# EL_Sequencer.net
KiCad netlist of a schematic drawn in EAGLE
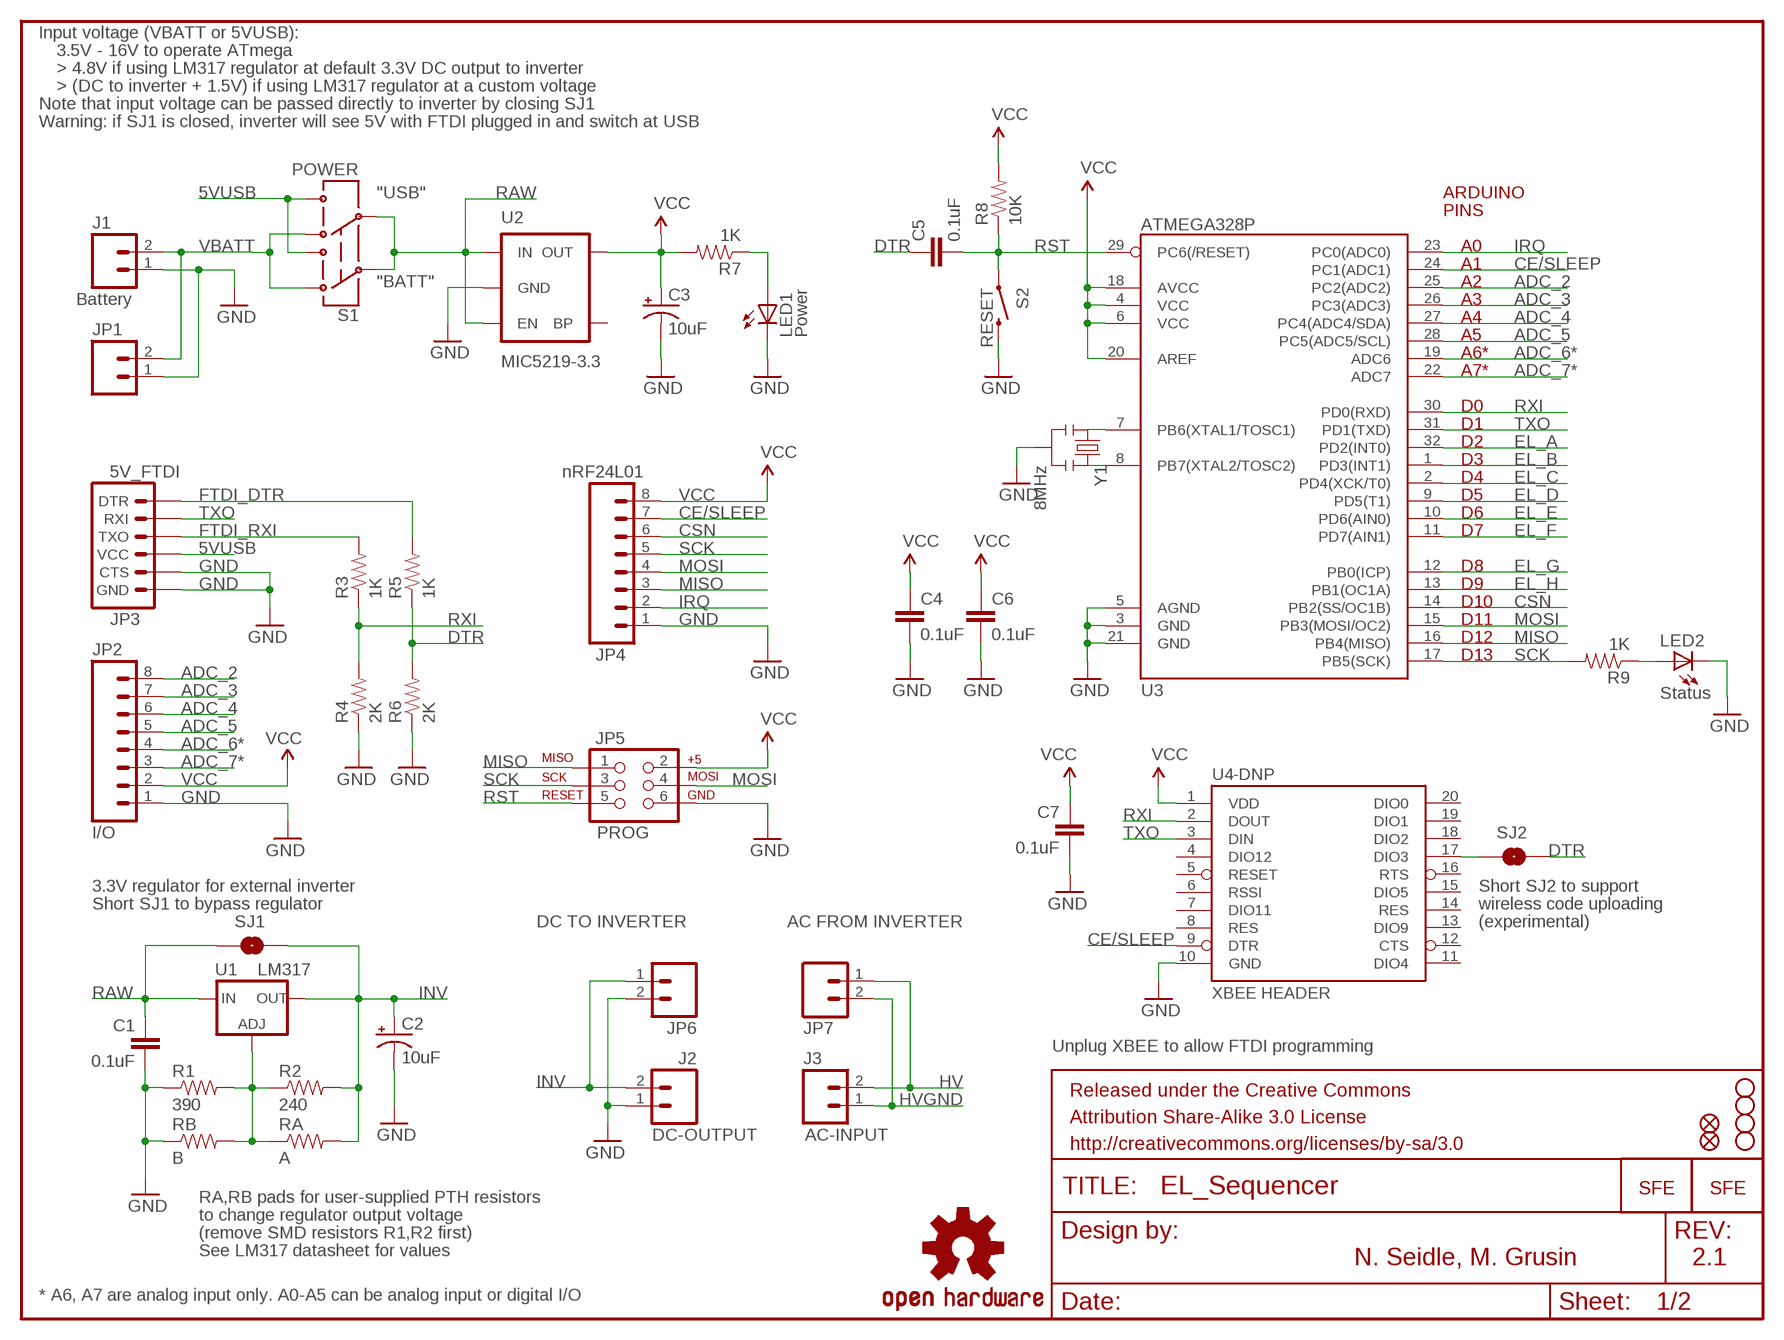
[diagram p0: schematic, sheet 1]
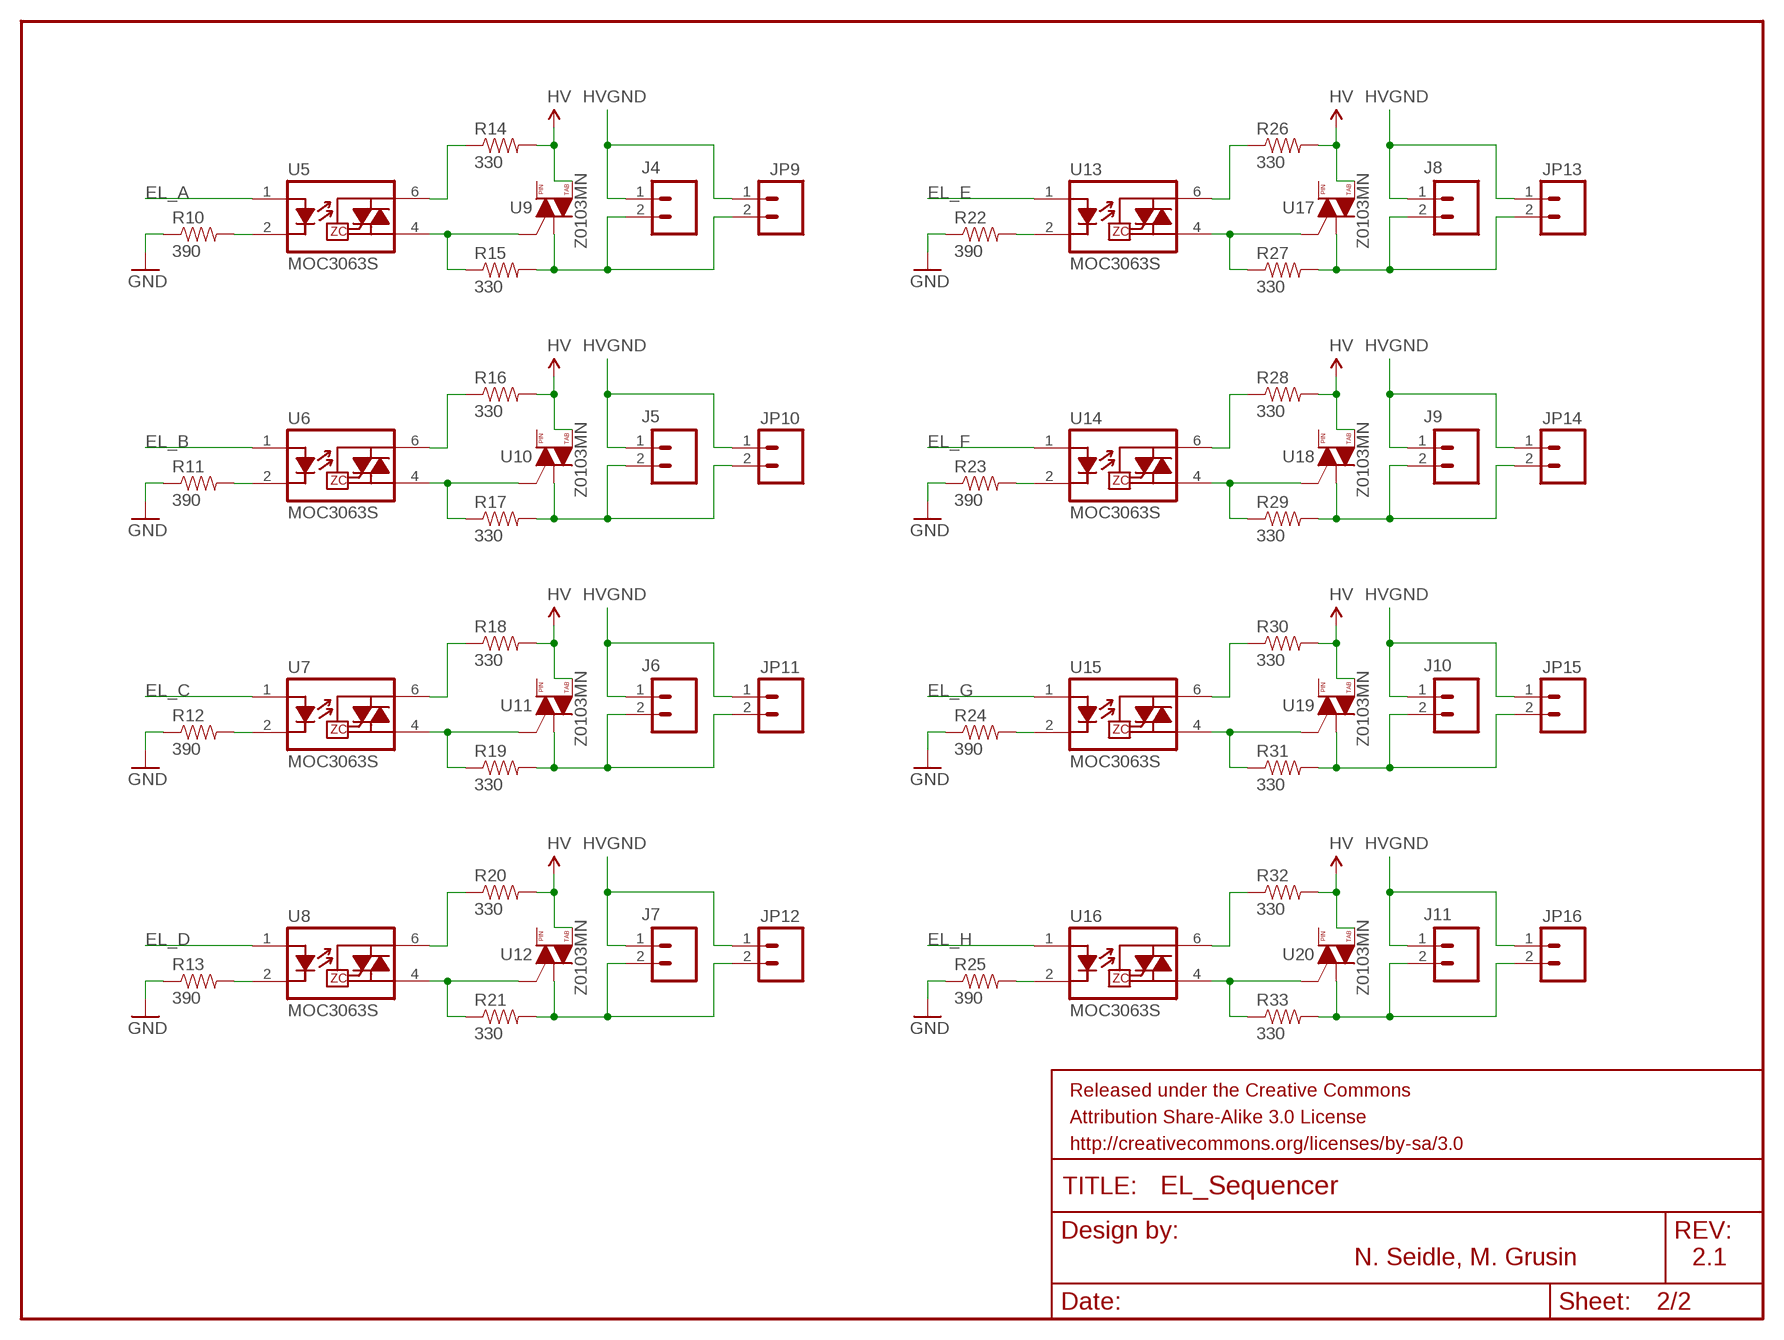
[diagram p1: schematic, sheet 2]

(export (version "E")
  (design (tool "Eeschema 10.0.6"))
  (components
    (comp (ref "C1")
      (value "0.1uF")
      (footprint "eagle-import:0402-CAP")
      (libsource (lib "eagle-import") (part "CAP0402-CAP"))
    )
    (comp (ref "C2")
      (value "10uF")
      (footprint "eagle-import:EIA3216")
      (libsource (lib "eagle-import") (part "CAP_POL1206"))
    )
    (comp (ref "C3")
      (value "10uF")
      (footprint "eagle-import:EIA3216")
      (libsource (lib "eagle-import") (part "CAP_POL1206"))
    )
    (comp (ref "C4")
      (value "0.1uF")
      (footprint "eagle-import:0402-CAP")
      (libsource (lib "eagle-import") (part "CAP0402-CAP"))
    )
    (comp (ref "C5")
      (value "0.1uF")
      (footprint "eagle-import:0402-CAP")
      (libsource (lib "eagle-import") (part "CAP0402-CAP"))
    )
    (comp (ref "C6")
      (value "0.1uF")
      (footprint "eagle-import:0402-CAP")
      (libsource (lib "eagle-import") (part "CAP0402-CAP"))
    )
    (comp (ref "C7")
      (value "0.1uF")
      (footprint "eagle-import:0402-CAP")
      (libsource (lib "eagle-import") (part "CAP0402-CAP"))
    )
    (comp (ref "FRAME1")
      (value "FRAME-LETTER")
      (footprint "eagle-import:CREATIVE_COMMONS")
      (libsource (lib "eagle-import") (part "FRAME-LETTER"))
    )
    (comp (ref "J1")
      (value "Battery")
      (footprint "eagle-import:JST-2-SMD")
      (libsource (lib "eagle-import") (part "M02-JST-2MM-SMT"))
    )
    (comp (ref "J2")
      (value "DC-OUTPUT")
      (footprint "eagle-import:JST-2-SMD")
      (libsource (lib "eagle-import") (part "M02-JST-2MM-SMT"))
    )
    (comp (ref "J3")
      (value "AC-INPUT")
      (footprint "eagle-import:JST-2-SMD")
      (libsource (lib "eagle-import") (part "M02-JST-2MM-SMT"))
    )
    (comp (ref "JP1")
      (value "M02PTH")
      (footprint "eagle-import:1X02")
      (libsource (lib "eagle-import") (part "M02PTH"))
    )
    (comp (ref "JP2")
      (value "I/O")
      (footprint "eagle-import:1X08_ROUND")
      (libsource (lib "eagle-import") (part "M08_ROUND"))
    )
    (comp (ref "JP3")
      (value "5V_FTDI")
      (footprint "eagle-import:1X06")
      (libsource (lib "eagle-import") (part "ARDUINO_SERIAL_PROGRAMPTH"))
    )
    (comp (ref "JP4")
      (value "nRF24L01")
      (footprint "eagle-import:1X08")
      (libsource (lib "eagle-import") (part "M081X08"))
    )
    (comp (ref "JP5")
      (value "PROG")
      (footprint "eagle-import:2X3")
      (libsource (lib "eagle-import") (part "AVR_SPI_PRG_6PTH"))
    )
    (comp (ref "JP6")
      (value "M02PTH")
      (footprint "eagle-import:1X02")
      (libsource (lib "eagle-import") (part "M02PTH"))
    )
    (comp (ref "JP7")
      (value "M02PTH")
      (footprint "eagle-import:1X02")
      (libsource (lib "eagle-import") (part "M02PTH"))
    )
    (comp (ref "JP8")
      (value "LOGO-SFESK")
      (footprint "eagle-import:SFE-LOGO-FLAME")
      (libsource (lib "eagle-import") (part "SparkFun-Aesthetics_LOGO-SFESK"))
    )
    (comp (ref "LED1")
      (value "Power")
      (footprint "eagle-import:LED-0603")
      (libsource (lib "eagle-import") (part "LED0603"))
    )
    (comp (ref "LED2")
      (value "Status")
      (footprint "eagle-import:LED-0603")
      (libsource (lib "eagle-import") (part "LED0603"))
    )
    (comp (ref "R1")
      (value "390")
      (footprint "eagle-import:0603-RES")
      (libsource (lib "eagle-import") (part "RESISTOR0603-RES"))
    )
    (comp (ref "R2")
      (value "240")
      (footprint "eagle-import:0603-RES")
      (libsource (lib "eagle-import") (part "RESISTOR0603-RES"))
    )
    (comp (ref "R3")
      (value "1K")
      (footprint "eagle-import:0402-RES")
      (libsource (lib "eagle-import") (part "RESISTOR0402-RES"))
    )
    (comp (ref "R4")
      (value "2K")
      (footprint "eagle-import:0402-RES")
      (libsource (lib "eagle-import") (part "RESISTOR0402-RES"))
    )
    (comp (ref "R5")
      (value "1K")
      (footprint "eagle-import:0402-RES")
      (libsource (lib "eagle-import") (part "RESISTOR0402-RES"))
    )
    (comp (ref "R6")
      (value "2K")
      (footprint "eagle-import:0402-RES")
      (libsource (lib "eagle-import") (part "RESISTOR0402-RES"))
    )
    (comp (ref "R7")
      (value "1K")
      (footprint "eagle-import:0402-RES")
      (libsource (lib "eagle-import") (part "RESISTOR0402-RES"))
    )
    (comp (ref "R8")
      (value "10K")
      (footprint "eagle-import:0402-RES")
      (libsource (lib "eagle-import") (part "RESISTOR0402-RES"))
    )
    (comp (ref "R9")
      (value "1K")
      (footprint "eagle-import:0402-RES")
      (libsource (lib "eagle-import") (part "RESISTOR0402-RES"))
    )
    (comp (ref "RA")
      (value "A")
      (footprint "eagle-import:AXIAL-0.4")
      (libsource (lib "eagle-import") (part "RESISTORPTH-1/4W"))
    )
    (comp (ref "RB")
      (value "B")
      (footprint "eagle-import:AXIAL-0.4")
      (libsource (lib "eagle-import") (part "RESISTORPTH-1/4W"))
    )
    (comp (ref "S1")
      (value "POWER")
      (footprint "eagle-import:AYZ0202")
      (libsource (lib "eagle-import") (part "SWITCH-DPDTSMD"))
    )
    (comp (ref "S2")
      (value "RESET")
      (footprint "eagle-import:TACTILE_SWITCH_SMD")
      (libsource (lib "eagle-import") (part "SWITCH-MOMENTARY-2SMD"))
    )
    (comp (ref "SJ1")
      (value "SOLDERJUMPERROUND")
      (footprint "eagle-import:SJ_ROUND")
      (libsource (lib "eagle-import") (part "SOLDERJUMPERROUND"))
    )
    (comp (ref "SJ2")
      (value "SOLDERJUMPERNO")
      (footprint "eagle-import:SJ_2S-NO")
      (libsource (lib "eagle-import") (part "SOLDERJUMPERNO"))
    )
    (comp (ref "U$1")
      (value "OSHW-LOGOS")
      (footprint "eagle-import:OSHW-LOGO-S")
      (libsource (lib "eagle-import") (part "OSHW-LOGOS"))
    )
    (comp (ref "U$2")
      (value "LOGO-SFENEW")
      (footprint "eagle-import:SFE-NEW-WEBLOGO")
      (libsource (lib "eagle-import") (part "LOGO-SFENEW"))
    )
    (comp (ref "U$3")
      (value "FIDUCIALUFIDUCIAL")
      (footprint "eagle-import:MICRO-FIDUCIAL")
      (libsource (lib "eagle-import") (part "FIDUCIALUFIDUCIAL"))
    )
    (comp (ref "U$4")
      (value "FIDUCIALUFIDUCIAL")
      (footprint "eagle-import:MICRO-FIDUCIAL")
      (libsource (lib "eagle-import") (part "FIDUCIALUFIDUCIAL"))
    )
    (comp (ref "U$5")
      (value "STAND-OFF")
      (footprint "eagle-import:STAND-OFF")
      (libsource (lib "eagle-import") (part "STAND-OFF"))
    )
    (comp (ref "U$6")
      (value "STAND-OFF")
      (footprint "eagle-import:STAND-OFF")
      (libsource (lib "eagle-import") (part "STAND-OFF"))
    )
    (comp (ref "U$7")
      (value "STAND-OFF")
      (footprint "eagle-import:STAND-OFF")
      (libsource (lib "eagle-import") (part "STAND-OFF"))
    )
    (comp (ref "U$8")
      (value "STAND-OFF")
      (footprint "eagle-import:STAND-OFF")
      (libsource (lib "eagle-import") (part "STAND-OFF"))
    )
    (comp (ref "U1")
      (value "LM317")
      (footprint "eagle-import:V-REG_DPACK")
      (libsource (lib "eagle-import") (part "V_REG_317DPACK"))
    )
    (comp (ref "U2")
      (value "MIC5219-3.3")
      (footprint "eagle-import:SOT23-5")
      (libsource (lib "eagle-import") (part "V_REG_LDOSMD"))
    )
    (comp (ref "U3")
      (value "ATMEGA328P")
      (footprint "eagle-import:TQFP32-08")
      (libsource (lib "eagle-import") (part "ATMEGA168"))
    )
    (comp (ref "U4-DNP")
      (value "XBEE HEADER")
      (footprint "eagle-import:XBEE-LONGPAD")
      (libsource (lib "eagle-import") (part "XBEE-1LONGPAD"))
    )
    (comp (ref "Y1")
      (value "8MHz")
      (footprint "eagle-import:RESONATOR-SMD")
      (libsource (lib "eagle-import") (part "RESONATORSMD"))
    )
    (comp (ref "FRAME2")
      (value "FRAME-LETTER")
      (footprint "eagle-import:CREATIVE_COMMONS")
      (libsource (lib "eagle-import") (part "FRAME-LETTER"))
    )
    (comp (ref "J4")
      (value "M02-JST-2MM-SMT")
      (footprint "eagle-import:JST-2-SMD")
      (libsource (lib "eagle-import") (part "M02-JST-2MM-SMT"))
    )
    (comp (ref "J5")
      (value "M02-JST-2MM-SMT")
      (footprint "eagle-import:JST-2-SMD")
      (libsource (lib "eagle-import") (part "M02-JST-2MM-SMT"))
    )
    (comp (ref "J6")
      (value "M02-JST-2MM-SMT")
      (footprint "eagle-import:JST-2-SMD")
      (libsource (lib "eagle-import") (part "M02-JST-2MM-SMT"))
    )
    (comp (ref "J7")
      (value "M02-JST-2MM-SMT")
      (footprint "eagle-import:JST-2-SMD")
      (libsource (lib "eagle-import") (part "M02-JST-2MM-SMT"))
    )
    (comp (ref "J8")
      (value "M02-JST-2MM-SMT")
      (footprint "eagle-import:JST-2-SMD")
      (libsource (lib "eagle-import") (part "M02-JST-2MM-SMT"))
    )
    (comp (ref "J9")
      (value "M02-JST-2MM-SMT")
      (footprint "eagle-import:JST-2-SMD")
      (libsource (lib "eagle-import") (part "M02-JST-2MM-SMT"))
    )
    (comp (ref "J10")
      (value "M02-JST-2MM-SMT")
      (footprint "eagle-import:JST-2-SMD")
      (libsource (lib "eagle-import") (part "M02-JST-2MM-SMT"))
    )
    (comp (ref "J11")
      (value "M02-JST-2MM-SMT")
      (footprint "eagle-import:JST-2-SMD")
      (libsource (lib "eagle-import") (part "M02-JST-2MM-SMT"))
    )
    (comp (ref "JP9")
      (value "M02PTH")
      (footprint "eagle-import:1X02")
      (libsource (lib "eagle-import") (part "M02PTH"))
    )
    (comp (ref "JP10")
      (value "M02PTH")
      (footprint "eagle-import:1X02")
      (libsource (lib "eagle-import") (part "M02PTH"))
    )
    (comp (ref "JP11")
      (value "M02PTH")
      (footprint "eagle-import:1X02")
      (libsource (lib "eagle-import") (part "M02PTH"))
    )
    (comp (ref "JP12")
      (value "M02PTH")
      (footprint "eagle-import:1X02")
      (libsource (lib "eagle-import") (part "M02PTH"))
    )
    (comp (ref "JP13")
      (value "M02PTH")
      (footprint "eagle-import:1X02")
      (libsource (lib "eagle-import") (part "M02PTH"))
    )
    (comp (ref "JP14")
      (value "M02PTH")
      (footprint "eagle-import:1X02")
      (libsource (lib "eagle-import") (part "M02PTH"))
    )
    (comp (ref "JP15")
      (value "M02PTH")
      (footprint "eagle-import:1X02")
      (libsource (lib "eagle-import") (part "M02PTH"))
    )
    (comp (ref "JP16")
      (value "M02PTH")
      (footprint "eagle-import:1X02")
      (libsource (lib "eagle-import") (part "M02PTH"))
    )
    (comp (ref "R10")
      (value "390")
      (footprint "eagle-import:0402-RES")
      (libsource (lib "eagle-import") (part "RESISTOR0402-RES"))
    )
    (comp (ref "R11")
      (value "390")
      (footprint "eagle-import:0402-RES")
      (libsource (lib "eagle-import") (part "RESISTOR0402-RES"))
    )
    (comp (ref "R12")
      (value "390")
      (footprint "eagle-import:0402-RES")
      (libsource (lib "eagle-import") (part "RESISTOR0402-RES"))
    )
    (comp (ref "R13")
      (value "390")
      (footprint "eagle-import:0402-RES")
      (libsource (lib "eagle-import") (part "RESISTOR0402-RES"))
    )
    (comp (ref "R14")
      (value "330")
      (footprint "eagle-import:0603-RES")
      (libsource (lib "eagle-import") (part "RESISTOR0603-RES"))
    )
    (comp (ref "R15")
      (value "330")
      (footprint "eagle-import:0603-RES")
      (libsource (lib "eagle-import") (part "RESISTOR0603-RES"))
    )
    (comp (ref "R16")
      (value "330")
      (footprint "eagle-import:0603-RES")
      (libsource (lib "eagle-import") (part "RESISTOR0603-RES"))
    )
    (comp (ref "R17")
      (value "330")
      (footprint "eagle-import:0603-RES")
      (libsource (lib "eagle-import") (part "RESISTOR0603-RES"))
    )
    (comp (ref "R18")
      (value "330")
      (footprint "eagle-import:0603-RES")
      (libsource (lib "eagle-import") (part "RESISTOR0603-RES"))
    )
    (comp (ref "R19")
      (value "330")
      (footprint "eagle-import:0603-RES")
      (libsource (lib "eagle-import") (part "RESISTOR0603-RES"))
    )
    (comp (ref "R20")
      (value "330")
      (footprint "eagle-import:0603-RES")
      (libsource (lib "eagle-import") (part "RESISTOR0603-RES"))
    )
    (comp (ref "R21")
      (value "330")
      (footprint "eagle-import:0603-RES")
      (libsource (lib "eagle-import") (part "RESISTOR0603-RES"))
    )
    (comp (ref "R22")
      (value "390")
      (footprint "eagle-import:0402-RES")
      (libsource (lib "eagle-import") (part "RESISTOR0402-RES"))
    )
    (comp (ref "R23")
      (value "390")
      (footprint "eagle-import:0402-RES")
      (libsource (lib "eagle-import") (part "RESISTOR0402-RES"))
    )
    (comp (ref "R24")
      (value "390")
      (footprint "eagle-import:0402-RES")
      (libsource (lib "eagle-import") (part "RESISTOR0402-RES"))
    )
    (comp (ref "R25")
      (value "390")
      (footprint "eagle-import:0402-RES")
      (libsource (lib "eagle-import") (part "RESISTOR0402-RES"))
    )
    (comp (ref "R26")
      (value "330")
      (footprint "eagle-import:0603-RES")
      (libsource (lib "eagle-import") (part "RESISTOR0603-RES"))
    )
    (comp (ref "R27")
      (value "330")
      (footprint "eagle-import:0603-RES")
      (libsource (lib "eagle-import") (part "RESISTOR0603-RES"))
    )
    (comp (ref "R28")
      (value "330")
      (footprint "eagle-import:0603-RES")
      (libsource (lib "eagle-import") (part "RESISTOR0603-RES"))
    )
    (comp (ref "R29")
      (value "330")
      (footprint "eagle-import:0603-RES")
      (libsource (lib "eagle-import") (part "RESISTOR0603-RES"))
    )
    (comp (ref "R30")
      (value "330")
      (footprint "eagle-import:0603-RES")
      (libsource (lib "eagle-import") (part "RESISTOR0603-RES"))
    )
    (comp (ref "R31")
      (value "330")
      (footprint "eagle-import:0603-RES")
      (libsource (lib "eagle-import") (part "RESISTOR0603-RES"))
    )
    (comp (ref "R32")
      (value "330")
      (footprint "eagle-import:0603-RES")
      (libsource (lib "eagle-import") (part "RESISTOR0603-RES"))
    )
    (comp (ref "R33")
      (value "330")
      (footprint "eagle-import:0603-RES")
      (libsource (lib "eagle-import") (part "RESISTOR0603-RES"))
    )
    (comp (ref "U5")
      (value "MOC3063S")
      (footprint "eagle-import:DIP8SMD")
      (libsource (lib "eagle-import") (part "MOC3063S"))
    )
    (comp (ref "U6")
      (value "MOC3063S")
      (footprint "eagle-import:DIP8SMD")
      (libsource (lib "eagle-import") (part "MOC3063S"))
    )
    (comp (ref "U7")
      (value "MOC3063S")
      (footprint "eagle-import:DIP8SMD")
      (libsource (lib "eagle-import") (part "MOC3063S"))
    )
    (comp (ref "U8")
      (value "MOC3063S")
      (footprint "eagle-import:DIP8SMD")
      (libsource (lib "eagle-import") (part "MOC3063S"))
    )
    (comp (ref "U9")
      (value "Z0103MN")
      (footprint "eagle-import:SOT223")
      (libsource (lib "eagle-import") (part "TRIACSMD"))
    )
    (comp (ref "U10")
      (value "Z0103MN")
      (footprint "eagle-import:SOT223")
      (libsource (lib "eagle-import") (part "TRIACSMD"))
    )
    (comp (ref "U11")
      (value "Z0103MN")
      (footprint "eagle-import:SOT223")
      (libsource (lib "eagle-import") (part "TRIACSMD"))
    )
    (comp (ref "U12")
      (value "Z0103MN")
      (footprint "eagle-import:SOT223")
      (libsource (lib "eagle-import") (part "TRIACSMD"))
    )
    (comp (ref "U13")
      (value "MOC3063S")
      (footprint "eagle-import:DIP8SMD")
      (libsource (lib "eagle-import") (part "MOC3063S"))
    )
    (comp (ref "U14")
      (value "MOC3063S")
      (footprint "eagle-import:DIP8SMD")
      (libsource (lib "eagle-import") (part "MOC3063S"))
    )
    (comp (ref "U15")
      (value "MOC3063S")
      (footprint "eagle-import:DIP8SMD")
      (libsource (lib "eagle-import") (part "MOC3063S"))
    )
    (comp (ref "U16")
      (value "MOC3063S")
      (footprint "eagle-import:DIP8SMD")
      (libsource (lib "eagle-import") (part "MOC3063S"))
    )
    (comp (ref "U17")
      (value "Z0103MN")
      (footprint "eagle-import:SOT223")
      (libsource (lib "eagle-import") (part "TRIACSMD"))
    )
    (comp (ref "U18")
      (value "Z0103MN")
      (footprint "eagle-import:SOT223")
      (libsource (lib "eagle-import") (part "TRIACSMD"))
    )
    (comp (ref "U19")
      (value "Z0103MN")
      (footprint "eagle-import:SOT223")
      (libsource (lib "eagle-import") (part "TRIACSMD"))
    )
    (comp (ref "U20")
      (value "Z0103MN")
      (footprint "eagle-import:SOT223")
      (libsource (lib "eagle-import") (part "TRIACSMD"))
    )
  )
  (nets
    (net (code "1") (name "5VUSB") (class "Default")
      (node (ref "JP3") (pin "4") (pinfunction "VCC_4") (pintype "passive"))
      (node (ref "S1") (pin "3") (pinfunction "3_3") (pintype "bidirectional"))
      (node (ref "S1") (pin "6") (pinfunction "6_6") (pintype "bidirectional"))
    )
    (net (code "2") (name "ADC_2") (class "Default")
      (node (ref "JP2") (pin "8") (pinfunction "8_8") (pintype "passive"))
      (node (ref "U3") (pin "25") (pinfunction "PC2(ADC2)_25") (pintype "bidirectional"))
    )
    (net (code "3") (name "ADC_3") (class "Default")
      (node (ref "JP2") (pin "7") (pinfunction "7_7") (pintype "passive"))
      (node (ref "U3") (pin "26") (pinfunction "PC3(ADC3)_26") (pintype "bidirectional"))
    )
    (net (code "4") (name "ADC_4") (class "Default")
      (node (ref "JP2") (pin "6") (pinfunction "6_6") (pintype "passive"))
      (node (ref "U3") (pin "27") (pinfunction "PC4(ADC4/SDA)_27") (pintype "bidirectional"))
    )
    (net (code "5") (name "ADC_5") (class "Default")
      (node (ref "JP2") (pin "5") (pinfunction "5_5") (pintype "passive"))
      (node (ref "U3") (pin "28") (pinfunction "PC5(ADC5/SCL)_28") (pintype "bidirectional"))
    )
    (net (code "6") (name "ADC_6*") (class "Default")
      (node (ref "JP2") (pin "4") (pinfunction "4_4") (pintype "passive"))
      (node (ref "U3") (pin "19") (pinfunction "ADC6_19") (pintype "bidirectional"))
    )
    (net (code "7") (name "ADC_7*") (class "Default")
      (node (ref "JP2") (pin "3") (pinfunction "3_3") (pintype "passive"))
      (node (ref "U3") (pin "22") (pinfunction "ADC7_22") (pintype "bidirectional"))
    )
    (net (code "8") (name "CE{slash}SLEEP") (class "Default")
      (node (ref "JP4") (pin "7") (pinfunction "7_7") (pintype "passive"))
      (node (ref "U3") (pin "24") (pinfunction "PC1(ADC1)_24") (pintype "bidirectional"))
      (node (ref "U4-DNP") (pin "9") (pinfunction "DTR_9") (pintype "bidirectional"))
    )
    (net (code "9") (name "CSN") (class "Default")
      (node (ref "JP4") (pin "6") (pinfunction "6_6") (pintype "passive"))
      (node (ref "U3") (pin "14") (pinfunction "PB2(SS/OC1B)_14") (pintype "bidirectional"))
    )
    (net (code "10") (name "DTR") (class "Default")
      (node (ref "C5") (pin "1") (pinfunction "1_1") (pintype "passive"))
      (node (ref "R5") (pin "1") (pinfunction "1_1") (pintype "passive"))
      (node (ref "R6") (pin "2") (pinfunction "2_2") (pintype "passive"))
      (node (ref "SJ2") (pin "2") (pinfunction "2_2") (pintype "passive"))
    )
    (net (code "11") (name "EL_A") (class "Default")
      (node (ref "U3") (pin "32") (pinfunction "PD2(INT0)_32") (pintype "bidirectional"))
      (node (ref "U5") (pin "1") (pinfunction "A_1") (pintype "bidirectional"))
    )
    (net (code "12") (name "EL_B") (class "Default")
      (node (ref "U3") (pin "1") (pinfunction "PD3(INT1)_1") (pintype "bidirectional"))
      (node (ref "U6") (pin "1") (pinfunction "A_1") (pintype "bidirectional"))
    )
    (net (code "13") (name "EL_C") (class "Default")
      (node (ref "U3") (pin "2") (pinfunction "PD4(XCK/T0)_2") (pintype "bidirectional"))
      (node (ref "U7") (pin "1") (pinfunction "A_1") (pintype "bidirectional"))
    )
    (net (code "14") (name "EL_D") (class "Default")
      (node (ref "U3") (pin "9") (pinfunction "PD5(T1)_9") (pintype "bidirectional"))
      (node (ref "U8") (pin "1") (pinfunction "A_1") (pintype "bidirectional"))
    )
    (net (code "15") (name "EL_E") (class "Default")
      (node (ref "U13") (pin "1") (pinfunction "A_1") (pintype "bidirectional"))
      (node (ref "U3") (pin "10") (pinfunction "PD6(AIN0)_10") (pintype "bidirectional"))
    )
    (net (code "16") (name "EL_F") (class "Default")
      (node (ref "U14") (pin "1") (pinfunction "A_1") (pintype "bidirectional"))
      (node (ref "U3") (pin "11") (pinfunction "PD7(AIN1)_11") (pintype "bidirectional"))
    )
    (net (code "17") (name "EL_G") (class "Default")
      (node (ref "U15") (pin "1") (pinfunction "A_1") (pintype "bidirectional"))
      (node (ref "U3") (pin "12") (pinfunction "PB0(ICP)_12") (pintype "bidirectional"))
    )
    (net (code "18") (name "EL_H") (class "Default")
      (node (ref "U16") (pin "1") (pinfunction "A_1") (pintype "bidirectional"))
      (node (ref "U3") (pin "13") (pinfunction "PB1(OC1A)_13") (pintype "bidirectional"))
    )
    (net (code "19") (name "FTDI_DTR") (class "Default")
      (node (ref "JP3") (pin "1") (pinfunction "DTR_1") (pintype "passive"))
      (node (ref "R5") (pin "2") (pinfunction "2_2") (pintype "passive"))
    )
    (net (code "20") (name "FTDI_RXI") (class "Default")
      (node (ref "JP3") (pin "3") (pinfunction "TXO_3") (pintype "passive"))
      (node (ref "R3") (pin "2") (pinfunction "2_2") (pintype "passive"))
    )
    (net (code "21") (name "GND") (class "Default")
      (node (ref "C1") (pin "2") (pinfunction "2_2") (pintype "passive"))
      (node (ref "C2") (pin "C") (pinfunction "-_C") (pintype "passive"))
      (node (ref "C3") (pin "C") (pinfunction "-_C") (pintype "passive"))
      (node (ref "C4") (pin "2") (pinfunction "2_2") (pintype "passive"))
      (node (ref "C6") (pin "2") (pinfunction "2_2") (pintype "passive"))
      (node (ref "C7") (pin "2") (pinfunction "2_2") (pintype "passive"))
      (node (ref "J1") (pin "1") (pinfunction "1_1") (pintype "passive"))
      (node (ref "J2") (pin "1") (pinfunction "1_1") (pintype "passive"))
      (node (ref "JP1") (pin "1") (pinfunction "1_1") (pintype "passive"))
      (node (ref "JP2") (pin "1") (pinfunction "1_1") (pintype "passive"))
      (node (ref "JP3") (pin "5") (pinfunction "CTS_5") (pintype "passive"))
      (node (ref "JP3") (pin "6") (pinfunction "GND_6") (pintype "passive"))
      (node (ref "JP4") (pin "1") (pinfunction "1_1") (pintype "passive"))
      (node (ref "JP5") (pin "6") (pinfunction "6_6") (pintype "passive"))
      (node (ref "JP6") (pin "2") (pinfunction "2_2") (pintype "passive"))
      (node (ref "LED1") (pin "C") (pinfunction "C_C") (pintype "passive"))
      (node (ref "LED2") (pin "C") (pinfunction "C_C") (pintype "passive"))
      (node (ref "R1") (pin "1") (pinfunction "1_1") (pintype "passive"))
      (node (ref "R10") (pin "1") (pinfunction "1_1") (pintype "passive"))
      (node (ref "R11") (pin "1") (pinfunction "1_1") (pintype "passive"))
      (node (ref "R12") (pin "1") (pinfunction "1_1") (pintype "passive"))
      (node (ref "R13") (pin "1") (pinfunction "1_1") (pintype "passive"))
      (node (ref "R22") (pin "1") (pinfunction "1_1") (pintype "passive"))
      (node (ref "R23") (pin "1") (pinfunction "1_1") (pintype "passive"))
      (node (ref "R24") (pin "1") (pinfunction "1_1") (pintype "passive"))
      (node (ref "R25") (pin "1") (pinfunction "1_1") (pintype "passive"))
      (node (ref "R4") (pin "1") (pinfunction "1_1") (pintype "passive"))
      (node (ref "R6") (pin "1") (pinfunction "1_1") (pintype "passive"))
      (node (ref "RB") (pin "P$1") (pinfunction "1_P$1") (pintype "passive"))
      (node (ref "S2") (pin "3") (pinfunction "2_3") (pintype "passive"))
      (node (ref "U2") (pin "2") (pinfunction "GND_2") (pintype "input"))
      (node (ref "U3") (pin "21") (pinfunction "GND_21") (pintype "bidirectional"))
      (node (ref "U3") (pin "3") (pinfunction "GND_3") (pintype "bidirectional"))
      (node (ref "U3") (pin "5") (pinfunction "AGND_5") (pintype "bidirectional"))
      (node (ref "U4-DNP") (pin "10") (pinfunction "GND_10") (pintype "power_in"))
      (node (ref "Y1") (pin "2") (pinfunction "2_2") (pintype "passive"))
    )
    (net (code "22") (name "HV") (class "Default")
      (node (ref "J3") (pin "2") (pinfunction "2_2") (pintype "passive"))
      (node (ref "JP7") (pin "1") (pinfunction "1_1") (pintype "passive"))
      (node (ref "R14") (pin "2") (pinfunction "2_2") (pintype "passive"))
      (node (ref "R16") (pin "2") (pinfunction "2_2") (pintype "passive"))
      (node (ref "R18") (pin "2") (pinfunction "2_2") (pintype "passive"))
      (node (ref "R20") (pin "2") (pinfunction "2_2") (pintype "passive"))
      (node (ref "R26") (pin "2") (pinfunction "2_2") (pintype "passive"))
      (node (ref "R28") (pin "2") (pinfunction "2_2") (pintype "passive"))
      (node (ref "R30") (pin "2") (pinfunction "2_2") (pintype "passive"))
      (node (ref "R32") (pin "2") (pinfunction "2_2") (pintype "passive"))
      (node (ref "U10") (pin "4") (pinfunction "T2_4") (pintype "passive"))
      (node (ref "U11") (pin "4") (pinfunction "T2_4") (pintype "passive"))
      (node (ref "U12") (pin "4") (pinfunction "T2_4") (pintype "passive"))
      (node (ref "U17") (pin "4") (pinfunction "T2_4") (pintype "passive"))
      (node (ref "U18") (pin "4") (pinfunction "T2_4") (pintype "passive"))
      (node (ref "U19") (pin "4") (pinfunction "T2_4") (pintype "passive"))
      (node (ref "U20") (pin "4") (pinfunction "T2_4") (pintype "passive"))
      (node (ref "U9") (pin "4") (pinfunction "T2_4") (pintype "passive"))
    )
    (net (code "23") (name "HVGND") (class "Default")
      (node (ref "J10") (pin "1") (pinfunction "1_1") (pintype "passive"))
      (node (ref "J11") (pin "1") (pinfunction "1_1") (pintype "passive"))
      (node (ref "J3") (pin "1") (pinfunction "1_1") (pintype "passive"))
      (node (ref "J4") (pin "1") (pinfunction "1_1") (pintype "passive"))
      (node (ref "J5") (pin "1") (pinfunction "1_1") (pintype "passive"))
      (node (ref "J6") (pin "1") (pinfunction "1_1") (pintype "passive"))
      (node (ref "J7") (pin "1") (pinfunction "1_1") (pintype "passive"))
      (node (ref "J8") (pin "1") (pinfunction "1_1") (pintype "passive"))
      (node (ref "J9") (pin "1") (pinfunction "1_1") (pintype "passive"))
      (node (ref "JP10") (pin "1") (pinfunction "1_1") (pintype "passive"))
      (node (ref "JP11") (pin "1") (pinfunction "1_1") (pintype "passive"))
      (node (ref "JP12") (pin "1") (pinfunction "1_1") (pintype "passive"))
      (node (ref "JP13") (pin "1") (pinfunction "1_1") (pintype "passive"))
      (node (ref "JP14") (pin "1") (pinfunction "1_1") (pintype "passive"))
      (node (ref "JP15") (pin "1") (pinfunction "1_1") (pintype "passive"))
      (node (ref "JP16") (pin "1") (pinfunction "1_1") (pintype "passive"))
      (node (ref "JP7") (pin "2") (pinfunction "2_2") (pintype "passive"))
      (node (ref "JP9") (pin "1") (pinfunction "1_1") (pintype "passive"))
    )
    (net (code "24") (name "INV") (class "Default")
      (node (ref "C2") (pin "A") (pinfunction "+_A") (pintype "passive"))
      (node (ref "J2") (pin "2") (pinfunction "2_2") (pintype "passive"))
      (node (ref "JP6") (pin "1") (pinfunction "1_1") (pintype "passive"))
      (node (ref "R2") (pin "2") (pinfunction "2_2") (pintype "passive"))
      (node (ref "RA") (pin "P$2") (pinfunction "2_P$2") (pintype "passive"))
      (node (ref "SJ1") (pin "2") (pinfunction "2_2") (pintype "passive"))
      (node (ref "U1") (pin "4") (pinfunction "OUT_4") (pintype "output"))
    )
    (net (code "25") (name "IRQ") (class "Default")
      (node (ref "JP4") (pin "2") (pinfunction "2_2") (pintype "passive"))
      (node (ref "U3") (pin "23") (pinfunction "PC0(ADC0)_23") (pintype "bidirectional"))
    )
    (net (code "26") (name "MISO") (class "Default")
      (node (ref "JP4") (pin "3") (pinfunction "3_3") (pintype "passive"))
      (node (ref "JP5") (pin "1") (pinfunction "1_1") (pintype "passive"))
      (node (ref "U3") (pin "16") (pinfunction "PB4(MISO)_16") (pintype "bidirectional"))
    )
    (net (code "27") (name "MOSI") (class "Default")
      (node (ref "JP4") (pin "4") (pinfunction "4_4") (pintype "passive"))
      (node (ref "JP5") (pin "4") (pinfunction "4_4") (pintype "passive"))
      (node (ref "U3") (pin "15") (pinfunction "PB3(MOSI/OC2)_15") (pintype "bidirectional"))
    )
    (net (code "28") (name "Net-(LED1-PadA)") (class "Default")
      (node (ref "LED1") (pin "A") (pinfunction "A_A") (pintype "passive"))
      (node (ref "R7") (pin "1") (pinfunction "1_1") (pintype "passive"))
    )
    (net (code "29") (name "Net-(LED2-PadA)") (class "Default")
      (node (ref "LED2") (pin "A") (pinfunction "A_A") (pintype "passive"))
      (node (ref "R9") (pin "1") (pinfunction "1_1") (pintype "passive"))
    )
    (net (code "30") (name "Net-(RA-1)") (class "Default")
      (node (ref "R1") (pin "2") (pinfunction "2_2") (pintype "passive"))
      (node (ref "R2") (pin "1") (pinfunction "1_1") (pintype "passive"))
      (node (ref "RA") (pin "P$1") (pinfunction "1_P$1") (pintype "passive"))
      (node (ref "RB") (pin "P$2") (pinfunction "2_P$2") (pintype "passive"))
      (node (ref "U1") (pin "1") (pinfunction "ADJ_1") (pintype "input"))
    )
    (net (code "31") (name "Net-(U3-PB6(XTAL1{slash}TOSC1))") (class "Default")
      (node (ref "U3") (pin "7") (pinfunction "PB6(XTAL1/TOSC1)_7") (pintype "bidirectional"))
      (node (ref "Y1") (pin "1") (pinfunction "1_1") (pintype "passive"))
    )
    (net (code "32") (name "Net-(U3-PB7(XTAL2{slash}TOSC2))") (class "Default")
      (node (ref "U3") (pin "8") (pinfunction "PB7(XTAL2/TOSC2)_8") (pintype "bidirectional"))
      (node (ref "Y1") (pin "3") (pinfunction "3_3") (pintype "passive"))
    )
    (net (code "33") (name "Net-(U4-DNP-DIO3)") (class "Default")
      (node (ref "SJ2") (pin "1") (pinfunction "1_1") (pintype "passive"))
      (node (ref "U4-DNP") (pin "17") (pinfunction "DIO3_17") (pintype "bidirectional"))
    )
    (net (code "34") (name "Net-(U5-K)") (class "Default")
      (node (ref "R10") (pin "2") (pinfunction "2_2") (pintype "passive"))
      (node (ref "U5") (pin "2") (pinfunction "K_2") (pintype "bidirectional"))
    )
    (net (code "35") (name "Net-(U5-T1)") (class "Default")
      (node (ref "R14") (pin "1") (pinfunction "1_1") (pintype "passive"))
      (node (ref "U5") (pin "6") (pinfunction "T1_6") (pintype "bidirectional"))
    )
    (net (code "36") (name "Net-(U5-T2)") (class "Default")
      (node (ref "R15") (pin "1") (pinfunction "1_1") (pintype "passive"))
      (node (ref "U5") (pin "4") (pinfunction "T2_4") (pintype "bidirectional"))
      (node (ref "U9") (pin "3") (pinfunction "G_3") (pintype "bidirectional"))
    )
    (net (code "37") (name "Net-(U6-K)") (class "Default")
      (node (ref "R11") (pin "2") (pinfunction "2_2") (pintype "passive"))
      (node (ref "U6") (pin "2") (pinfunction "K_2") (pintype "bidirectional"))
    )
    (net (code "38") (name "Net-(U6-T1)") (class "Default")
      (node (ref "R16") (pin "1") (pinfunction "1_1") (pintype "passive"))
      (node (ref "U6") (pin "6") (pinfunction "T1_6") (pintype "bidirectional"))
    )
    (net (code "39") (name "Net-(U7-K)") (class "Default")
      (node (ref "R12") (pin "2") (pinfunction "2_2") (pintype "passive"))
      (node (ref "U7") (pin "2") (pinfunction "K_2") (pintype "bidirectional"))
    )
    (net (code "40") (name "Net-(U7-T1)") (class "Default")
      (node (ref "R18") (pin "1") (pinfunction "1_1") (pintype "passive"))
      (node (ref "U7") (pin "6") (pinfunction "T1_6") (pintype "bidirectional"))
    )
    (net (code "41") (name "Net-(U8-K)") (class "Default")
      (node (ref "R13") (pin "2") (pinfunction "2_2") (pintype "passive"))
      (node (ref "U8") (pin "2") (pinfunction "K_2") (pintype "bidirectional"))
    )
    (net (code "42") (name "Net-(U8-T1)") (class "Default")
      (node (ref "R20") (pin "1") (pinfunction "1_1") (pintype "passive"))
      (node (ref "U8") (pin "6") (pinfunction "T1_6") (pintype "bidirectional"))
    )
    (net (code "43") (name "Net-(U9-T1)") (class "Default")
      (node (ref "J4") (pin "2") (pinfunction "2_2") (pintype "passive"))
      (node (ref "JP9") (pin "2") (pinfunction "2_2") (pintype "passive"))
      (node (ref "R15") (pin "2") (pinfunction "2_2") (pintype "passive"))
      (node (ref "U9") (pin "1") (pinfunction "T1_1") (pintype "bidirectional"))
    )
    (net (code "44") (name "Net-(U10-G)") (class "Default")
      (node (ref "R17") (pin "1") (pinfunction "1_1") (pintype "passive"))
      (node (ref "U10") (pin "3") (pinfunction "G_3") (pintype "bidirectional"))
      (node (ref "U6") (pin "4") (pinfunction "T2_4") (pintype "bidirectional"))
    )
    (net (code "45") (name "Net-(U10-T1)") (class "Default")
      (node (ref "J5") (pin "2") (pinfunction "2_2") (pintype "passive"))
      (node (ref "JP10") (pin "2") (pinfunction "2_2") (pintype "passive"))
      (node (ref "R17") (pin "2") (pinfunction "2_2") (pintype "passive"))
      (node (ref "U10") (pin "1") (pinfunction "T1_1") (pintype "bidirectional"))
    )
    (net (code "46") (name "Net-(U11-G)") (class "Default")
      (node (ref "R19") (pin "1") (pinfunction "1_1") (pintype "passive"))
      (node (ref "U11") (pin "3") (pinfunction "G_3") (pintype "bidirectional"))
      (node (ref "U7") (pin "4") (pinfunction "T2_4") (pintype "bidirectional"))
    )
    (net (code "47") (name "Net-(U11-T1)") (class "Default")
      (node (ref "J6") (pin "2") (pinfunction "2_2") (pintype "passive"))
      (node (ref "JP11") (pin "2") (pinfunction "2_2") (pintype "passive"))
      (node (ref "R19") (pin "2") (pinfunction "2_2") (pintype "passive"))
      (node (ref "U11") (pin "1") (pinfunction "T1_1") (pintype "bidirectional"))
    )
    (net (code "48") (name "Net-(U12-G)") (class "Default")
      (node (ref "R21") (pin "1") (pinfunction "1_1") (pintype "passive"))
      (node (ref "U12") (pin "3") (pinfunction "G_3") (pintype "bidirectional"))
      (node (ref "U8") (pin "4") (pinfunction "T2_4") (pintype "bidirectional"))
    )
    (net (code "49") (name "Net-(U12-T1)") (class "Default")
      (node (ref "J7") (pin "2") (pinfunction "2_2") (pintype "passive"))
      (node (ref "JP12") (pin "2") (pinfunction "2_2") (pintype "passive"))
      (node (ref "R21") (pin "2") (pinfunction "2_2") (pintype "passive"))
      (node (ref "U12") (pin "1") (pinfunction "T1_1") (pintype "bidirectional"))
    )
    (net (code "50") (name "Net-(U13-K)") (class "Default")
      (node (ref "R22") (pin "2") (pinfunction "2_2") (pintype "passive"))
      (node (ref "U13") (pin "2") (pinfunction "K_2") (pintype "bidirectional"))
    )
    (net (code "51") (name "Net-(U13-T1)") (class "Default")
      (node (ref "R26") (pin "1") (pinfunction "1_1") (pintype "passive"))
      (node (ref "U13") (pin "6") (pinfunction "T1_6") (pintype "bidirectional"))
    )
    (net (code "52") (name "Net-(U13-T2)") (class "Default")
      (node (ref "R27") (pin "1") (pinfunction "1_1") (pintype "passive"))
      (node (ref "U13") (pin "4") (pinfunction "T2_4") (pintype "bidirectional"))
      (node (ref "U17") (pin "3") (pinfunction "G_3") (pintype "bidirectional"))
    )
    (net (code "53") (name "Net-(U14-K)") (class "Default")
      (node (ref "R23") (pin "2") (pinfunction "2_2") (pintype "passive"))
      (node (ref "U14") (pin "2") (pinfunction "K_2") (pintype "bidirectional"))
    )
    (net (code "54") (name "Net-(U14-T1)") (class "Default")
      (node (ref "R28") (pin "1") (pinfunction "1_1") (pintype "passive"))
      (node (ref "U14") (pin "6") (pinfunction "T1_6") (pintype "bidirectional"))
    )
    (net (code "55") (name "Net-(U14-T2)") (class "Default")
      (node (ref "R29") (pin "1") (pinfunction "1_1") (pintype "passive"))
      (node (ref "U14") (pin "4") (pinfunction "T2_4") (pintype "bidirectional"))
      (node (ref "U18") (pin "3") (pinfunction "G_3") (pintype "bidirectional"))
    )
    (net (code "56") (name "Net-(U15-K)") (class "Default")
      (node (ref "R24") (pin "2") (pinfunction "2_2") (pintype "passive"))
      (node (ref "U15") (pin "2") (pinfunction "K_2") (pintype "bidirectional"))
    )
    (net (code "57") (name "Net-(U15-T1)") (class "Default")
      (node (ref "R30") (pin "1") (pinfunction "1_1") (pintype "passive"))
      (node (ref "U15") (pin "6") (pinfunction "T1_6") (pintype "bidirectional"))
    )
    (net (code "58") (name "Net-(U15-T2)") (class "Default")
      (node (ref "R31") (pin "1") (pinfunction "1_1") (pintype "passive"))
      (node (ref "U15") (pin "4") (pinfunction "T2_4") (pintype "bidirectional"))
      (node (ref "U19") (pin "3") (pinfunction "G_3") (pintype "bidirectional"))
    )
    (net (code "59") (name "Net-(U16-K)") (class "Default")
      (node (ref "R25") (pin "2") (pinfunction "2_2") (pintype "passive"))
      (node (ref "U16") (pin "2") (pinfunction "K_2") (pintype "bidirectional"))
    )
    (net (code "60") (name "Net-(U16-T1)") (class "Default")
      (node (ref "R32") (pin "1") (pinfunction "1_1") (pintype "passive"))
      (node (ref "U16") (pin "6") (pinfunction "T1_6") (pintype "bidirectional"))
    )
    (net (code "61") (name "Net-(U16-T2)") (class "Default")
      (node (ref "R33") (pin "1") (pinfunction "1_1") (pintype "passive"))
      (node (ref "U16") (pin "4") (pinfunction "T2_4") (pintype "bidirectional"))
      (node (ref "U20") (pin "3") (pinfunction "G_3") (pintype "bidirectional"))
    )
    (net (code "62") (name "Net-(U17-T1)") (class "Default")
      (node (ref "J8") (pin "2") (pinfunction "2_2") (pintype "passive"))
      (node (ref "JP13") (pin "2") (pinfunction "2_2") (pintype "passive"))
      (node (ref "R27") (pin "2") (pinfunction "2_2") (pintype "passive"))
      (node (ref "U17") (pin "1") (pinfunction "T1_1") (pintype "bidirectional"))
    )
    (net (code "63") (name "Net-(U18-T1)") (class "Default")
      (node (ref "J9") (pin "2") (pinfunction "2_2") (pintype "passive"))
      (node (ref "JP14") (pin "2") (pinfunction "2_2") (pintype "passive"))
      (node (ref "R29") (pin "2") (pinfunction "2_2") (pintype "passive"))
      (node (ref "U18") (pin "1") (pinfunction "T1_1") (pintype "bidirectional"))
    )
    (net (code "64") (name "Net-(U19-T1)") (class "Default")
      (node (ref "J10") (pin "2") (pinfunction "2_2") (pintype "passive"))
      (node (ref "JP15") (pin "2") (pinfunction "2_2") (pintype "passive"))
      (node (ref "R31") (pin "2") (pinfunction "2_2") (pintype "passive"))
      (node (ref "U19") (pin "1") (pinfunction "T1_1") (pintype "bidirectional"))
    )
    (net (code "65") (name "Net-(U20-T1)") (class "Default")
      (node (ref "J11") (pin "2") (pinfunction "2_2") (pintype "passive"))
      (node (ref "JP16") (pin "2") (pinfunction "2_2") (pintype "passive"))
      (node (ref "R33") (pin "2") (pinfunction "2_2") (pintype "passive"))
      (node (ref "U20") (pin "1") (pinfunction "T1_1") (pintype "bidirectional"))
    )
    (net (code "66") (name "RAW") (class "Default")
      (node (ref "C1") (pin "1") (pinfunction "1_1") (pintype "passive"))
      (node (ref "S1") (pin "2") (pinfunction "2_2") (pintype "bidirectional"))
      (node (ref "S1") (pin "5") (pinfunction "5_5") (pintype "bidirectional"))
      (node (ref "SJ1") (pin "1") (pinfunction "1_1") (pintype "passive"))
      (node (ref "U1") (pin "3") (pinfunction "IN_3") (pintype "input"))
      (node (ref "U2") (pin "1") (pinfunction "IN_1") (pintype "input"))
      (node (ref "U2") (pin "3") (pinfunction "EN_3") (pintype "input"))
    )
    (net (code "67") (name "RST") (class "Default")
      (node (ref "C5") (pin "2") (pinfunction "2_2") (pintype "passive"))
      (node (ref "JP5") (pin "5") (pinfunction "5_5") (pintype "passive"))
      (node (ref "R8") (pin "1") (pinfunction "1_1") (pintype "passive"))
      (node (ref "S2") (pin "1") (pinfunction "1_1") (pintype "passive"))
      (node (ref "U3") (pin "29") (pinfunction "PC6(/RESET)_29") (pintype "bidirectional"))
    )
    (net (code "68") (name "RXI") (class "Default")
      (node (ref "R3") (pin "1") (pinfunction "1_1") (pintype "passive"))
      (node (ref "R4") (pin "2") (pinfunction "2_2") (pintype "passive"))
      (node (ref "U3") (pin "30") (pinfunction "PD0(RXD)_30") (pintype "bidirectional"))
      (node (ref "U4-DNP") (pin "2") (pinfunction "DOUT_2") (pintype "output"))
    )
    (net (code "69") (name "SCK") (class "Default")
      (node (ref "JP4") (pin "5") (pinfunction "5_5") (pintype "passive"))
      (node (ref "JP5") (pin "3") (pinfunction "3_3") (pintype "passive"))
      (node (ref "R9") (pin "2") (pinfunction "2_2") (pintype "passive"))
      (node (ref "U3") (pin "17") (pinfunction "PB5(SCK)_17") (pintype "bidirectional"))
    )
    (net (code "70") (name "TXO") (class "Default")
      (node (ref "JP3") (pin "2") (pinfunction "RXI_2") (pintype "passive"))
      (node (ref "U3") (pin "31") (pinfunction "PD1(TXD)_31") (pintype "bidirectional"))
      (node (ref "U4-DNP") (pin "3") (pinfunction "DIN_3") (pintype "input"))
    )
    (net (code "71") (name "VBATT") (class "Default")
      (node (ref "J1") (pin "2") (pinfunction "2_2") (pintype "passive"))
      (node (ref "JP1") (pin "2") (pinfunction "2_2") (pintype "passive"))
      (node (ref "S1") (pin "1") (pinfunction "1_1") (pintype "bidirectional"))
      (node (ref "S1") (pin "4") (pinfunction "4_4") (pintype "bidirectional"))
    )
    (net (code "72") (name "VCC") (class "Default")
      (node (ref "C3") (pin "A") (pinfunction "+_A") (pintype "passive"))
      (node (ref "C4") (pin "1") (pinfunction "1_1") (pintype "passive"))
      (node (ref "C6") (pin "1") (pinfunction "1_1") (pintype "passive"))
      (node (ref "C7") (pin "1") (pinfunction "1_1") (pintype "passive"))
      (node (ref "JP2") (pin "2") (pinfunction "2_2") (pintype "passive"))
      (node (ref "JP4") (pin "8") (pinfunction "8_8") (pintype "passive"))
      (node (ref "JP5") (pin "2") (pinfunction "2_2") (pintype "passive"))
      (node (ref "R7") (pin "2") (pinfunction "2_2") (pintype "passive"))
      (node (ref "R8") (pin "2") (pinfunction "2_2") (pintype "passive"))
      (node (ref "U2") (pin "5") (pinfunction "OUT_5") (pintype "passive"))
      (node (ref "U3") (pin "18") (pinfunction "AVCC_18") (pintype "bidirectional"))
      (node (ref "U3") (pin "20") (pinfunction "AREF_20") (pintype "bidirectional"))
      (node (ref "U3") (pin "4") (pinfunction "VCC_4") (pintype "bidirectional"))
      (node (ref "U3") (pin "6") (pinfunction "VCC_6") (pintype "bidirectional"))
      (node (ref "U4-DNP") (pin "1") (pinfunction "VDD_1") (pintype "power_in"))
    )
    (net (code "73") (name "unconnected-(U2-BP-Pad4)") (class "Default")
      (node (ref "U2") (pin "4") (pinfunction "BP_4") (pintype "input"))
    )
    (net (code "74") (name "unconnected-(U4-DNP-CTS-Pad12)") (class "Default")
      (node (ref "U4-DNP") (pin "12") (pinfunction "CTS_12") (pintype "output"))
    )
    (net (code "75") (name "unconnected-(U4-DNP-DIO0-Pad20)") (class "Default")
      (node (ref "U4-DNP") (pin "20") (pinfunction "DIO0_20") (pintype "bidirectional"))
    )
    (net (code "76") (name "unconnected-(U4-DNP-DIO1-Pad19)") (class "Default")
      (node (ref "U4-DNP") (pin "19") (pinfunction "DIO1_19") (pintype "bidirectional"))
    )
    (net (code "77") (name "unconnected-(U4-DNP-DIO2-Pad18)") (class "Default")
      (node (ref "U4-DNP") (pin "18") (pinfunction "DIO2_18") (pintype "bidirectional"))
    )
    (net (code "78") (name "unconnected-(U4-DNP-DIO4-Pad11)") (class "Default")
      (node (ref "U4-DNP") (pin "11") (pinfunction "DIO4_11") (pintype "bidirectional"))
    )
    (net (code "79") (name "unconnected-(U4-DNP-DIO5-Pad15)") (class "Default")
      (node (ref "U4-DNP") (pin "15") (pinfunction "DIO5_15") (pintype "bidirectional"))
    )
    (net (code "80") (name "unconnected-(U4-DNP-DIO9-Pad13)") (class "Default")
      (node (ref "U4-DNP") (pin "13") (pinfunction "DIO9_13") (pintype "bidirectional"))
    )
    (net (code "81") (name "unconnected-(U4-DNP-DIO11-Pad7)") (class "Default")
      (node (ref "U4-DNP") (pin "7") (pinfunction "DIO11_7") (pintype "bidirectional"))
    )
    (net (code "82") (name "unconnected-(U4-DNP-DIO12-Pad4)") (class "Default")
      (node (ref "U4-DNP") (pin "4") (pinfunction "DIO12_4") (pintype "bidirectional"))
    )
    (net (code "83") (name "unconnected-(U4-DNP-RES-Pad8)") (class "Default")
      (node (ref "U4-DNP") (pin "8") (pinfunction "RES_8") (pintype "bidirectional"))
    )
    (net (code "84") (name "unconnected-(U4-DNP-RES-Pad14)") (class "Default")
      (node (ref "U4-DNP") (pin "14") (pinfunction "RES_14") (pintype "bidirectional"))
    )
    (net (code "85") (name "unconnected-(U4-DNP-RESET-Pad5)") (class "Default")
      (node (ref "U4-DNP") (pin "5") (pinfunction "RESET_5") (pintype "input"))
    )
    (net (code "86") (name "unconnected-(U4-DNP-RSSI-Pad6)") (class "Default")
      (node (ref "U4-DNP") (pin "6") (pinfunction "RSSI_6") (pintype "bidirectional"))
    )
    (net (code "87") (name "unconnected-(U4-DNP-RTS-Pad16)") (class "Default")
      (node (ref "U4-DNP") (pin "16") (pinfunction "RTS_16") (pintype "input"))
    )
    (net (code "88") (name "unconnected-(U9-T2-Pad2)") (class "Default")
      (node (ref "U9") (pin "2") (pinfunction "T2_2") (pintype "passive"))
    )
    (net (code "89") (name "unconnected-(U10-T2-Pad2)") (class "Default")
      (node (ref "U10") (pin "2") (pinfunction "T2_2") (pintype "passive"))
    )
    (net (code "90") (name "unconnected-(U11-T2-Pad2)") (class "Default")
      (node (ref "U11") (pin "2") (pinfunction "T2_2") (pintype "passive"))
    )
    (net (code "91") (name "unconnected-(U12-T2-Pad2)") (class "Default")
      (node (ref "U12") (pin "2") (pinfunction "T2_2") (pintype "passive"))
    )
    (net (code "92") (name "unconnected-(U17-T2-Pad2)") (class "Default")
      (node (ref "U17") (pin "2") (pinfunction "T2_2") (pintype "passive"))
    )
    (net (code "93") (name "unconnected-(U18-T2-Pad2)") (class "Default")
      (node (ref "U18") (pin "2") (pinfunction "T2_2") (pintype "passive"))
    )
    (net (code "94") (name "unconnected-(U19-T2-Pad2)") (class "Default")
      (node (ref "U19") (pin "2") (pinfunction "T2_2") (pintype "passive"))
    )
    (net (code "95") (name "unconnected-(U20-T2-Pad2)") (class "Default")
      (node (ref "U20") (pin "2") (pinfunction "T2_2") (pintype "passive"))
    )
  )
)
